# main.net
KiCad netlist of a schematic drawn in Altium Designer
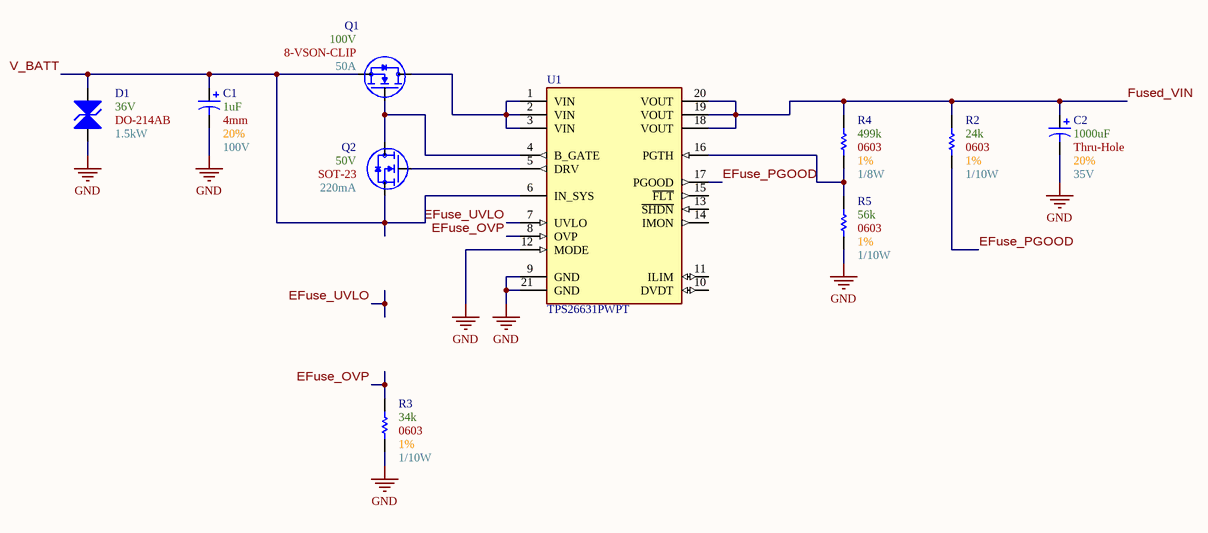
[diagram p0: main.SchDoc]

(export (version "E")
  (design (tool "Eeschema 10.0.6"))
  (components
    (comp (ref "C1")
      (value "[Cap] 4mm 1uF 20% 100V")
      (footprint "[Cap] SMD Polarized, 4mm")
      (description "865080840001")
      (fields
        (field (name "MAX VOLTAGE") "100V")
        (field (name "SIZE PACKAGE") "4mm")
        (field (name "TOLERANCE") "20%")
        (field (name "CAPACITANCE") "1uF")
      )
      (libsource (lib "Capacitors") (part "[Cap] 4mm 1uF 20% 100V"))
    )
    (comp (ref "C2")
      (value "[Cap] Thru-Hole 1000uF 20% 35V")
      (footprint "[Cap] Thru-Hole Polarized 10mm")
      (description "35PK1000MEFC10X20")
      (fields
        (field (name "MAX VOLTAGE") "35V")
        (field (name "SIZE PACKAGE") "Thru-Hole")
        (field (name "TOLERANCE") "20%")
        (field (name "CAPACITANCE") "1000uF")
      )
      (libsource (lib "Capacitors") (part "[Cap] Thru-Hole 1000uF 20% 35V"))
    )
    (comp (ref "D1")
      (value "DO-214AB")
      (footprint "DO-214AB")
      (description "SMCJ36CA")
      (fields (field (name "WATTAGE") "1.5kW") (field (name "OPTIMAL ZENER VOLTAGE") "36V"))
      (libsource (lib "Diodes") (part "[TVS] 36Vnom 40Vclamp_max"))
    )
    (comp (ref "Q1")
      (value "CSD19537Q3")
      (footprint "8-VSON-CLIP")
      (fields
        (field (name "IDS_MAX") "50A")
        (field (name "PACKAGE") "8-VSON-CLIP")
        (field (name "VDS_MAX") "100V")
      )
      (libsource (lib "Transistors") (part "[NMOS] SMD 100V 50A 14.5mOhm"))
    )
    (comp (ref "Q2")
      (value "[NMOS] SMD 50V 220mA 3mOhm")
      (footprint "SOT-23")
      (description "BSS138")
      (fields
        (field (name "IDS_MAX") "220mA")
        (field (name "PACKAGE") "SOT-23")
        (field (name "VDS_MAX") "50V")
      )
      (libsource (lib "Transistors") (part "[NMOS] SMD 50V 220mA 3mOhm"))
    )
    (comp (ref "R2")
      (value "[24k] SMD 0603 1% 1/10W")
      (footprint "[Res] SMD 0603")
      (description "RC0603FR-1324KL")
      (fields
        (field (name "WATTAGE") "1/10W")
        (field (name "TOLERANCE") "1%")
        (field (name "RESISTANCE") "24k")
        (field (name "SIZE PACKAGE") "0603")
      )
      (libsource (lib "Resistors") (part "[24k] SMD 0603 1% 1/10W"))
    )
    (comp (ref "R3")
      (value "[34k] SMD 0603 1% 1/10W")
      (footprint "[Res] SMD 0603")
      (description "RC0603FR-1334KL")
      (fields
        (field (name "WATTAGE") "1/10W")
        (field (name "TOLERANCE") "1%")
        (field (name "RESISTANCE") "34k")
        (field (name "SIZE PACKAGE") "0603")
      )
      (libsource (lib "Resistors") (part "[34k] SMD 0603 1% 1/10W"))
    )
    (comp (ref "R4")
      (value "[499k] SMD 0603 1% 1/8W")
      (footprint "[Res] SMD 0603")
      (description "CRCW0603499KFKEA")
      (fields
        (field (name "WATTAGE") "1/8W")
        (field (name "TOLERANCE") "1%")
        (field (name "RESISTANCE") "499k")
        (field (name "SIZE PACKAGE") "0603")
      )
      (libsource (lib "Resistors") (part "[499k] SMD 0603 1% 1/8W"))
    )
    (comp (ref "R5")
      (value "[56k] SMD 0603 1% 1/10W")
      (footprint "[Res] SMD 0603")
      (description "CRGCQ0603F56K")
      (fields
        (field (name "WATTAGE") "1/10W")
        (field (name "TOLERANCE") "1%")
        (field (name "RESISTANCE") "56k")
        (field (name "SIZE PACKAGE") "0603")
      )
      (libsource (lib "Resistors") (part "[56k] SMD 0603 1% 1/10W"))
    )
    (comp (ref "U1")
      (value "TPS26631PWPT")
      (footprint "[E-Fuse] 4.5-60V 6A")
      (libsource (lib "ICs") (part "[E-Fuse] 4.5-60V 6A"))
    )
  )
  (nets
    (net (code "1") (name "/EFuse_OVP") (class "Default")
      (node (ref "R3") (pin "2") (pinfunction "2_2") (pintype "passive"))
      (node (ref "U1") (pin "8") (pinfunction "OVP_8") (pintype "input"))
    )
    (net (code "2") (name "/EFuse_PGOOD") (class "Default")
      (node (ref "R2") (pin "1") (pinfunction "1_1") (pintype "passive"))
      (node (ref "U1") (pin "17") (pinfunction "PGOOD_17") (pintype "output"))
    )
    (net (code "3") (name "/EFuse_UVLO") (class "Default")
      (node (ref "U1") (pin "7") (pinfunction "UVLO_7") (pintype "input"))
    )
    (net (code "4") (name "/Fused_VIN") (class "Default")
      (node (ref "C2") (pin "1") (pinfunction "1_1") (pintype "passive"))
      (node (ref "R2") (pin "2") (pinfunction "2_2") (pintype "passive"))
      (node (ref "R4") (pin "2") (pinfunction "2_2") (pintype "passive"))
      (node (ref "U1") (pin "18") (pinfunction "VOUT_18") (pintype "passive"))
      (node (ref "U1") (pin "19") (pinfunction "VOUT_19") (pintype "passive"))
      (node (ref "U1") (pin "20") (pinfunction "VOUT_20") (pintype "passive"))
    )
    (net (code "5") (name "/V_BATT") (class "Default")
      (node (ref "C1") (pin "1") (pinfunction "1_1") (pintype "passive"))
      (node (ref "D1") (pin "1") (pinfunction "K_1") (pintype "passive"))
      (node (ref "Q1") (pin "2") (pinfunction "Source_2") (pintype "passive"))
      (node (ref "Q2") (pin "2") (pinfunction "Source_2") (pintype "passive"))
      (node (ref "U1") (pin "6") (pinfunction "IN_SYS_6") (pintype "power_in"))
    )
    (net (code "6") (name "GND") (class "Default")
      (node (ref "C1") (pin "2") (pinfunction "2_2") (pintype "passive"))
      (node (ref "C2") (pin "2") (pinfunction "2_2") (pintype "passive"))
      (node (ref "D1") (pin "2") (pinfunction "A_2") (pintype "passive"))
      (node (ref "R3") (pin "1") (pinfunction "1_1") (pintype "passive"))
      (node (ref "R5") (pin "1") (pinfunction "1_1") (pintype "passive"))
      (node (ref "U1") (pin "12") (pinfunction "MODE_12") (pintype "input"))
      (node (ref "U1") (pin "21") (pinfunction "GND_21") (pintype "power_in"))
      (node (ref "U1") (pin "9") (pinfunction "GND_9") (pintype "passive"))
    )
    (net (code "7") (name "Net-(Q1-Drain)") (class "Default")
      (node (ref "Q1") (pin "3") (pinfunction "Drain_3") (pintype "passive"))
      (node (ref "U1") (pin "1") (pinfunction "VIN_1") (pintype "passive"))
      (node (ref "U1") (pin "2") (pinfunction "VIN_2") (pintype "passive"))
      (node (ref "U1") (pin "3") (pinfunction "VIN_3") (pintype "passive"))
    )
    (net (code "8") (name "Net-(Q1-Gate)") (class "Default")
      (node (ref "Q1") (pin "1") (pinfunction "Gate_1") (pintype "passive"))
      (node (ref "Q2") (pin "3") (pinfunction "Drain_3") (pintype "passive"))
      (node (ref "U1") (pin "4") (pinfunction "B_GATE_4") (pintype "output"))
    )
    (net (code "9") (name "Net-(Q2-Gate)") (class "Default")
      (node (ref "Q2") (pin "1") (pinfunction "Gate_1") (pintype "passive"))
      (node (ref "U1") (pin "5") (pinfunction "DRV_5") (pintype "output"))
    )
    (net (code "10") (name "Net-(U1-PGTH)") (class "Default")
      (node (ref "R4") (pin "1") (pinfunction "1_1") (pintype "passive"))
      (node (ref "R5") (pin "2") (pinfunction "2_2") (pintype "passive"))
      (node (ref "U1") (pin "16") (pinfunction "PGTH_16") (pintype "input"))
    )
    (net (code "11") (name "unconnected-(U1-DVDT-Pad10)") (class "Default")
      (node (ref "U1") (pin "10") (pinfunction "DVDT_10") (pintype "bidirectional"))
    )
    (net (code "12") (name "unconnected-(U1-ILIM-Pad11)") (class "Default")
      (node (ref "U1") (pin "11") (pinfunction "ILIM_11") (pintype "bidirectional"))
    )
    (net (code "13") (name "unconnected-(U1-IMON-Pad14)") (class "Default")
      (node (ref "U1") (pin "14") (pinfunction "IMON_14") (pintype "output"))
    )
    (net (code "14") (name "unconnected-(U1-~{FLT}-Pad15)") (class "Default")
      (node (ref "U1") (pin "15") (pinfunction "~{FLT}_15") (pintype "output"))
    )
    (net (code "15") (name "unconnected-(U1-~{SHDN}-Pad13)") (class "Default")
      (node (ref "U1") (pin "13") (pinfunction "~{SHDN}_13") (pintype "input"))
    )
  )
)
